# nf10_addon.net
KiCad netlist of a schematic drawn in Altium Designer
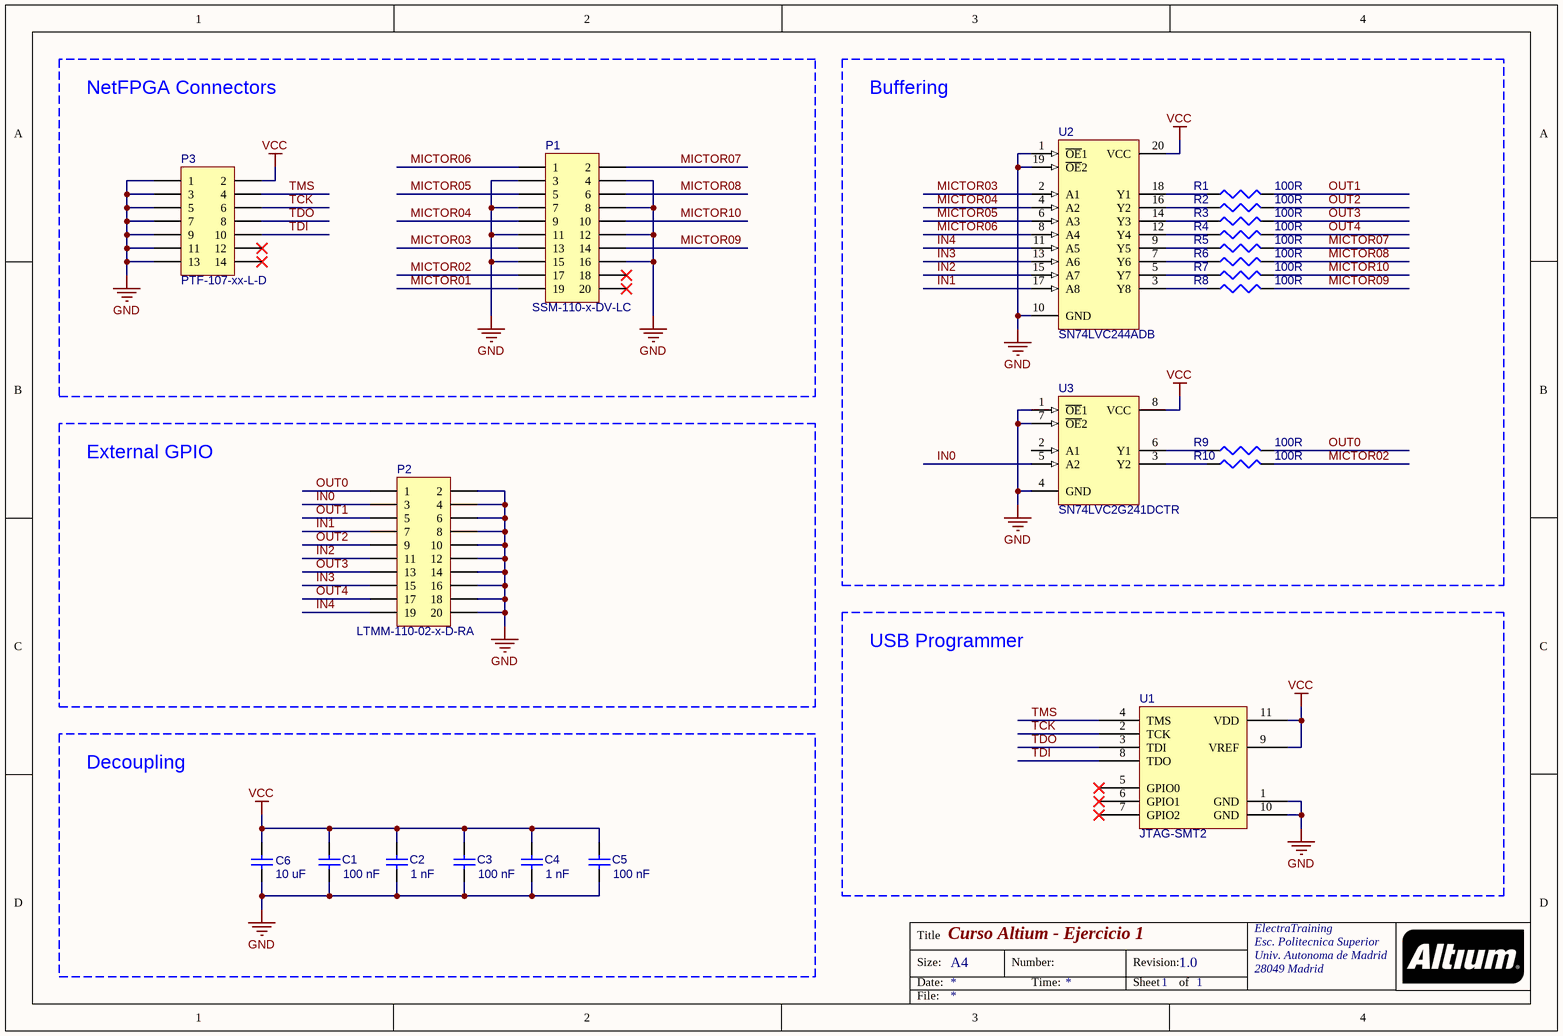
[diagram p0: nf10_addon.SchDoc]

(export (version "E")
  (design (tool "Eeschema 10.0.6"))
  (components
    (comp (ref "C1")
      (value "100 nF")
      (footprint "CAPC0603(1608)100_N")
      (description "Capacitor")
      (fields (field (name "Comment") "Cap") (field (name "PUBLISHER") "Altium Limited"))
      (libsource (lib "Miscellaneous Devices") (part "Cap"))
    )
    (comp (ref "C2")
      (value "1 nF")
      (footprint "CAPC0603(1608)100_N")
      (description "Capacitor")
      (fields (field (name "Comment") "Cap") (field (name "PUBLISHER") "Altium Limited"))
      (libsource (lib "Miscellaneous Devices") (part "Cap"))
    )
    (comp (ref "C3")
      (value "100 nF")
      (footprint "CAPC0603(1608)100_N")
      (description "Capacitor")
      (fields (field (name "Comment") "Cap") (field (name "PUBLISHER") "Altium Limited"))
      (libsource (lib "Miscellaneous Devices") (part "Cap"))
    )
    (comp (ref "C4")
      (value "1 nF")
      (footprint "CAPC0603(1608)100_N")
      (description "Capacitor")
      (fields (field (name "Comment") "Cap") (field (name "PUBLISHER") "Altium Limited"))
      (libsource (lib "Miscellaneous Devices") (part "Cap"))
    )
    (comp (ref "C5")
      (value "100 nF")
      (footprint "CAPC0603(1608)100_N")
      (description "Capacitor")
      (fields (field (name "Comment") "Cap") (field (name "PUBLISHER") "Altium Limited"))
      (libsource (lib "Miscellaneous Devices") (part "Cap"))
    )
    (comp (ref "C6")
      (value "10 uF")
      (footprint "CAPC1206(3216)100_N")
      (description "Capacitor")
      (fields (field (name "Comment") "Cap") (field (name "PUBLISHER") "Altium Limited"))
      (libsource (lib "Miscellaneous Devices") (part "Cap"))
    )
    (comp (ref "P1")
      (value "SSM-110-x-DV-LC")
      (footprint "SSM-110-X-DV-LC")
      (description "Samtec SSM-110-x-DV-LC")
      (fields (field (name "PUBLISHER") "Altium Limited"))
      (libsource (lib "nf10_addon") (part "SSM-110-x-DV-LC"))
    )
    (comp (ref "P2")
      (value "LTMM-110-02-x-D-RA")
      (footprint "LTMM-110-02-X-D-RA")
      (description "Samtec LTMM-110-02-x-D-RA")
      (fields (field (name "PUBLISHER") "Altium Limited"))
      (libsource (lib "nf10_addon") (part "LTMM-110-02-x-D-RA"))
    )
    (comp (ref "P3")
      (value "PTF-107-xx-L-D")
      (footprint "PTF-107-XX-L-D")
      (description "Samtec PTF-107-xx-L-D")
      (fields (field (name "PUBLISHER") "Altium Limited"))
      (libsource (lib "nf10_addon") (part "PTF-107-xx-L-D"))
    )
    (comp (ref "R1")
      (value "100R")
      (footprint "RESC0603(1608)_N")
      (description "Resistor")
      (fields (field (name "Comment") "Res3") (field (name "PUBLISHER") "Altium Limited"))
      (libsource (lib "Miscellaneous Devices") (part "Res3"))
    )
    (comp (ref "R2")
      (value "100R")
      (footprint "RESC0603(1608)_N")
      (description "Resistor")
      (fields (field (name "Comment") "Res3") (field (name "PUBLISHER") "Altium Limited"))
      (libsource (lib "Miscellaneous Devices") (part "Res3"))
    )
    (comp (ref "R3")
      (value "100R")
      (footprint "RESC0603(1608)_N")
      (description "Resistor")
      (fields (field (name "Comment") "Res3") (field (name "PUBLISHER") "Altium Limited"))
      (libsource (lib "Miscellaneous Devices") (part "Res3"))
    )
    (comp (ref "R4")
      (value "100R")
      (footprint "RESC0603(1608)_N")
      (description "Resistor")
      (fields (field (name "Comment") "Res3") (field (name "PUBLISHER") "Altium Limited"))
      (libsource (lib "Miscellaneous Devices") (part "Res3"))
    )
    (comp (ref "R5")
      (value "100R")
      (footprint "RESC0603(1608)_N")
      (description "Resistor")
      (fields (field (name "Comment") "Res3") (field (name "PUBLISHER") "Altium Limited"))
      (libsource (lib "Miscellaneous Devices") (part "Res3"))
    )
    (comp (ref "R6")
      (value "100R")
      (footprint "RESC0603(1608)_N")
      (description "Resistor")
      (fields (field (name "Comment") "Res3") (field (name "PUBLISHER") "Altium Limited"))
      (libsource (lib "Miscellaneous Devices") (part "Res3"))
    )
    (comp (ref "R7")
      (value "100R")
      (footprint "RESC0603(1608)_N")
      (description "Resistor")
      (fields (field (name "Comment") "Res3") (field (name "PUBLISHER") "Altium Limited"))
      (libsource (lib "Miscellaneous Devices") (part "Res3"))
    )
    (comp (ref "R8")
      (value "100R")
      (footprint "RESC0603(1608)_N")
      (description "Resistor")
      (fields (field (name "Comment") "Res3") (field (name "PUBLISHER") "Altium Limited"))
      (libsource (lib "Miscellaneous Devices") (part "Res3"))
    )
    (comp (ref "R9")
      (value "100R")
      (footprint "RESC0603(1608)_N")
      (description "Resistor")
      (fields (field (name "Comment") "Res3") (field (name "PUBLISHER") "Altium Limited"))
      (libsource (lib "Miscellaneous Devices") (part "Res3"))
    )
    (comp (ref "R10")
      (value "100R")
      (footprint "RESC0603(1608)_N")
      (description "Resistor")
      (fields (field (name "Comment") "Res3") (field (name "PUBLISHER") "Altium Limited"))
      (libsource (lib "Miscellaneous Devices") (part "Res3"))
    )
    (comp (ref "U1")
      (value "JTAG-SMT2")
      (footprint "JTAG-SMT2")
      (libsource (lib "NetFPGA10G_Addon") (part "JTAG_SMT2"))
    )
    (comp (ref "U2")
      (value "SN74LVC244ADB")
      (footprint "DB020_N")
      (description "Octal Buffer/Driver with 3-State Outputs")
      (fields (field (name "PUBLISHER") "Altium Limited"))
      (libsource (lib "TI Logic Buffer Line Driver") (part "SN74LVC244ADB"))
    )
    (comp (ref "U3")
      (value "SN74LVC2G241DCTR")
      (footprint "DCT08_N")
      (description "Quadruple Bus Buffer Gate with 3- State Outputs")
      (fields (field (name "PUBLISHER") "Altium Limited"))
      (libsource (lib "nf10_addon") (part "SN74LVC2G241DCTR"))
    )
  )
  (nets
    (net (code "1") (name "/IN0") (class "Default")
      (node (ref "P2") (pin "3") (pinfunction "3_3") (pintype "passive"))
      (node (ref "U3") (pin "5") (pinfunction "A2_5") (pintype "input"))
    )
    (net (code "2") (name "/IN1") (class "Default")
      (node (ref "P2") (pin "7") (pinfunction "7_7") (pintype "passive"))
      (node (ref "U2") (pin "17") (pinfunction "A8_17") (pintype "input"))
    )
    (net (code "3") (name "/IN2") (class "Default")
      (node (ref "P2") (pin "11") (pinfunction "11_11") (pintype "passive"))
      (node (ref "U2") (pin "15") (pinfunction "A7_15") (pintype "input"))
    )
    (net (code "4") (name "/IN3") (class "Default")
      (node (ref "P2") (pin "15") (pinfunction "15_15") (pintype "passive"))
      (node (ref "U2") (pin "13") (pinfunction "A6_13") (pintype "input"))
    )
    (net (code "5") (name "/IN4") (class "Default")
      (node (ref "P2") (pin "19") (pinfunction "19_19") (pintype "passive"))
      (node (ref "U2") (pin "11") (pinfunction "A5_11") (pintype "input"))
    )
    (net (code "6") (name "/MICTOR01") (class "Default")
      (node (ref "P1") (pin "19") (pinfunction "19_19") (pintype "passive"))
    )
    (net (code "7") (name "/MICTOR02") (class "Default")
      (node (ref "P1") (pin "17") (pinfunction "17_17") (pintype "passive"))
      (node (ref "R10") (pin "2") (pinfunction "2_2") (pintype "passive"))
    )
    (net (code "8") (name "/MICTOR03") (class "Default")
      (node (ref "P1") (pin "13") (pinfunction "13_13") (pintype "passive"))
      (node (ref "U2") (pin "2") (pinfunction "A1_2") (pintype "input"))
    )
    (net (code "9") (name "/MICTOR04") (class "Default")
      (node (ref "P1") (pin "9") (pinfunction "9_9") (pintype "passive"))
      (node (ref "U2") (pin "4") (pinfunction "A2_4") (pintype "input"))
    )
    (net (code "10") (name "/MICTOR05") (class "Default")
      (node (ref "P1") (pin "5") (pinfunction "5_5") (pintype "passive"))
      (node (ref "U2") (pin "6") (pinfunction "A3_6") (pintype "input"))
    )
    (net (code "11") (name "/MICTOR06") (class "Default")
      (node (ref "P1") (pin "1") (pinfunction "1_1") (pintype "passive"))
      (node (ref "U2") (pin "8") (pinfunction "A4_8") (pintype "input"))
    )
    (net (code "12") (name "/MICTOR07") (class "Default")
      (node (ref "P1") (pin "2") (pinfunction "2_2") (pintype "passive"))
      (node (ref "R5") (pin "2") (pinfunction "2_2") (pintype "passive"))
    )
    (net (code "13") (name "/MICTOR08") (class "Default")
      (node (ref "P1") (pin "6") (pinfunction "6_6") (pintype "passive"))
      (node (ref "R6") (pin "2") (pinfunction "2_2") (pintype "passive"))
    )
    (net (code "14") (name "/MICTOR09") (class "Default")
      (node (ref "P1") (pin "14") (pinfunction "14_14") (pintype "passive"))
      (node (ref "R8") (pin "2") (pinfunction "2_2") (pintype "passive"))
    )
    (net (code "15") (name "/MICTOR10") (class "Default")
      (node (ref "P1") (pin "10") (pinfunction "10_10") (pintype "passive"))
      (node (ref "R7") (pin "2") (pinfunction "2_2") (pintype "passive"))
    )
    (net (code "16") (name "/OUT0") (class "Default")
      (node (ref "P2") (pin "1") (pinfunction "1_1") (pintype "passive"))
      (node (ref "R9") (pin "2") (pinfunction "2_2") (pintype "passive"))
    )
    (net (code "17") (name "/OUT1") (class "Default")
      (node (ref "P2") (pin "5") (pinfunction "5_5") (pintype "passive"))
      (node (ref "R1") (pin "2") (pinfunction "2_2") (pintype "passive"))
    )
    (net (code "18") (name "/OUT2") (class "Default")
      (node (ref "P2") (pin "9") (pinfunction "9_9") (pintype "passive"))
      (node (ref "R2") (pin "2") (pinfunction "2_2") (pintype "passive"))
    )
    (net (code "19") (name "/OUT3") (class "Default")
      (node (ref "P2") (pin "13") (pinfunction "13_13") (pintype "passive"))
      (node (ref "R3") (pin "2") (pinfunction "2_2") (pintype "passive"))
    )
    (net (code "20") (name "/OUT4") (class "Default")
      (node (ref "P2") (pin "17") (pinfunction "17_17") (pintype "passive"))
      (node (ref "R4") (pin "2") (pinfunction "2_2") (pintype "passive"))
    )
    (net (code "21") (name "/TCK") (class "Default")
      (node (ref "P3") (pin "6") (pinfunction "6_6") (pintype "passive"))
      (node (ref "U1") (pin "2") (pinfunction "TCK_2") (pintype "passive"))
    )
    (net (code "22") (name "/TDI") (class "Default")
      (node (ref "P3") (pin "10") (pinfunction "10_10") (pintype "passive"))
      (node (ref "U1") (pin "8") (pinfunction "TDO_8") (pintype "passive"))
    )
    (net (code "23") (name "/TDO") (class "Default")
      (node (ref "P3") (pin "8") (pinfunction "8_8") (pintype "passive"))
      (node (ref "U1") (pin "3") (pinfunction "TDI_3") (pintype "passive"))
    )
    (net (code "24") (name "/TMS") (class "Default")
      (node (ref "P3") (pin "4") (pinfunction "4_4") (pintype "passive"))
      (node (ref "U1") (pin "4") (pinfunction "TMS_4") (pintype "passive"))
    )
    (net (code "25") (name "GND") (class "Default")
      (node (ref "C1") (pin "1") (pinfunction "1_1") (pintype "passive"))
      (node (ref "C2") (pin "1") (pinfunction "1_1") (pintype "passive"))
      (node (ref "C3") (pin "1") (pinfunction "1_1") (pintype "passive"))
      (node (ref "C4") (pin "1") (pinfunction "1_1") (pintype "passive"))
      (node (ref "C5") (pin "1") (pinfunction "1_1") (pintype "passive"))
      (node (ref "C6") (pin "1") (pinfunction "1_1") (pintype "passive"))
      (node (ref "P1") (pin "11") (pinfunction "11_11") (pintype "passive"))
      (node (ref "P1") (pin "12") (pinfunction "12_12") (pintype "passive"))
      (node (ref "P1") (pin "15") (pinfunction "15_15") (pintype "passive"))
      (node (ref "P1") (pin "16") (pinfunction "16_16") (pintype "passive"))
      (node (ref "P1") (pin "3") (pinfunction "3_3") (pintype "passive"))
      (node (ref "P1") (pin "4") (pinfunction "4_4") (pintype "passive"))
      (node (ref "P1") (pin "7") (pinfunction "7_7") (pintype "passive"))
      (node (ref "P1") (pin "8") (pinfunction "8_8") (pintype "passive"))
      (node (ref "P2") (pin "10") (pinfunction "10_10") (pintype "passive"))
      (node (ref "P2") (pin "12") (pinfunction "12_12") (pintype "passive"))
      (node (ref "P2") (pin "14") (pinfunction "14_14") (pintype "passive"))
      (node (ref "P2") (pin "16") (pinfunction "16_16") (pintype "passive"))
      (node (ref "P2") (pin "18") (pinfunction "18_18") (pintype "passive"))
      (node (ref "P2") (pin "2") (pinfunction "2_2") (pintype "passive"))
      (node (ref "P2") (pin "20") (pinfunction "20_20") (pintype "passive"))
      (node (ref "P2") (pin "4") (pinfunction "4_4") (pintype "passive"))
      (node (ref "P2") (pin "6") (pinfunction "6_6") (pintype "passive"))
      (node (ref "P2") (pin "8") (pinfunction "8_8") (pintype "passive"))
      (node (ref "P3") (pin "1") (pinfunction "1_1") (pintype "passive"))
      (node (ref "P3") (pin "11") (pinfunction "11_11") (pintype "passive"))
      (node (ref "P3") (pin "13") (pinfunction "13_13") (pintype "passive"))
      (node (ref "P3") (pin "3") (pinfunction "3_3") (pintype "passive"))
      (node (ref "P3") (pin "5") (pinfunction "5_5") (pintype "passive"))
      (node (ref "P3") (pin "7") (pinfunction "7_7") (pintype "passive"))
      (node (ref "P3") (pin "9") (pinfunction "9_9") (pintype "passive"))
      (node (ref "U1") (pin "1") (pinfunction "GND_1") (pintype "passive"))
      (node (ref "U1") (pin "10") (pinfunction "GND_10") (pintype "passive"))
      (node (ref "U2") (pin "1") (pinfunction "~{OE}1_1") (pintype "input"))
      (node (ref "U2") (pin "10") (pinfunction "GND_10") (pintype "power_in"))
      (node (ref "U2") (pin "19") (pinfunction "~{OE}2_19") (pintype "input"))
      (node (ref "U3") (pin "1") (pinfunction "~{OE}1_1") (pintype "input"))
      (node (ref "U3") (pin "4") (pinfunction "GND_4") (pintype "power_in"))
      (node (ref "U3") (pin "7") (pinfunction "~{OE}2_7") (pintype "input"))
    )
    (net (code "26") (name "Net-(U2-Y1)") (class "Default")
      (node (ref "R1") (pin "1") (pinfunction "1_1") (pintype "passive"))
      (node (ref "U2") (pin "18") (pinfunction "Y1_18") (pintype "tri_state"))
    )
    (net (code "27") (name "Net-(U2-Y2)") (class "Default")
      (node (ref "R2") (pin "1") (pinfunction "1_1") (pintype "passive"))
      (node (ref "U2") (pin "16") (pinfunction "Y2_16") (pintype "tri_state"))
    )
    (net (code "28") (name "Net-(U2-Y3)") (class "Default")
      (node (ref "R3") (pin "1") (pinfunction "1_1") (pintype "passive"))
      (node (ref "U2") (pin "14") (pinfunction "Y3_14") (pintype "tri_state"))
    )
    (net (code "29") (name "Net-(U2-Y4)") (class "Default")
      (node (ref "R4") (pin "1") (pinfunction "1_1") (pintype "passive"))
      (node (ref "U2") (pin "12") (pinfunction "Y4_12") (pintype "tri_state"))
    )
    (net (code "30") (name "Net-(U2-Y5)") (class "Default")
      (node (ref "R5") (pin "1") (pinfunction "1_1") (pintype "passive"))
      (node (ref "U2") (pin "9") (pinfunction "Y5_9") (pintype "tri_state"))
    )
    (net (code "31") (name "Net-(U2-Y6)") (class "Default")
      (node (ref "R6") (pin "1") (pinfunction "1_1") (pintype "passive"))
      (node (ref "U2") (pin "7") (pinfunction "Y6_7") (pintype "tri_state"))
    )
    (net (code "32") (name "Net-(U2-Y7)") (class "Default")
      (node (ref "R7") (pin "1") (pinfunction "1_1") (pintype "passive"))
      (node (ref "U2") (pin "5") (pinfunction "Y7_5") (pintype "tri_state"))
    )
    (net (code "33") (name "Net-(U2-Y8)") (class "Default")
      (node (ref "R8") (pin "1") (pinfunction "1_1") (pintype "passive"))
      (node (ref "U2") (pin "3") (pinfunction "Y8_3") (pintype "tri_state"))
    )
    (net (code "34") (name "Net-(U3-Y1)") (class "Default")
      (node (ref "R9") (pin "1") (pinfunction "1_1") (pintype "passive"))
      (node (ref "U3") (pin "6") (pinfunction "Y1_6") (pintype "tri_state"))
    )
    (net (code "35") (name "Net-(U3-Y2)") (class "Default")
      (node (ref "R10") (pin "1") (pinfunction "1_1") (pintype "passive"))
      (node (ref "U3") (pin "3") (pinfunction "Y2_3") (pintype "tri_state"))
    )
    (net (code "36") (name "VCC") (class "Default")
      (node (ref "C1") (pin "2") (pinfunction "2_2") (pintype "passive"))
      (node (ref "C2") (pin "2") (pinfunction "2_2") (pintype "passive"))
      (node (ref "C3") (pin "2") (pinfunction "2_2") (pintype "passive"))
      (node (ref "C4") (pin "2") (pinfunction "2_2") (pintype "passive"))
      (node (ref "C5") (pin "2") (pinfunction "2_2") (pintype "passive"))
      (node (ref "C6") (pin "2") (pinfunction "2_2") (pintype "passive"))
      (node (ref "P3") (pin "2") (pinfunction "2_2") (pintype "passive"))
      (node (ref "U1") (pin "11") (pinfunction "VDD_11") (pintype "passive"))
      (node (ref "U1") (pin "9") (pinfunction "VREF_9") (pintype "passive"))
      (node (ref "U2") (pin "20") (pinfunction "VCC_20") (pintype "power_in"))
      (node (ref "U3") (pin "8") (pinfunction "VCC_8") (pintype "power_in"))
    )
    (net (code "37") (name "unconnected-(P1-Pad18)") (class "Default")
      (node (ref "P1") (pin "18") (pinfunction "18_18") (pintype "passive+no_connect"))
    )
    (net (code "38") (name "unconnected-(P1-Pad20)") (class "Default")
      (node (ref "P1") (pin "20") (pinfunction "20_20") (pintype "passive+no_connect"))
    )
    (net (code "39") (name "unconnected-(P3-Pad12)") (class "Default")
      (node (ref "P3") (pin "12") (pinfunction "12_12") (pintype "passive+no_connect"))
    )
    (net (code "40") (name "unconnected-(P3-Pad14)") (class "Default")
      (node (ref "P3") (pin "14") (pinfunction "14_14") (pintype "passive+no_connect"))
    )
    (net (code "41") (name "unconnected-(U1-GPIO0-Pad5)") (class "Default")
      (node (ref "U1") (pin "5") (pinfunction "GPIO0_5") (pintype "passive+no_connect"))
    )
    (net (code "42") (name "unconnected-(U1-GPIO1-Pad6)") (class "Default")
      (node (ref "U1") (pin "6") (pinfunction "GPIO1_6") (pintype "passive+no_connect"))
    )
    (net (code "43") (name "unconnected-(U1-GPIO2-Pad7)") (class "Default")
      (node (ref "U1") (pin "7") (pinfunction "GPIO2_7") (pintype "passive+no_connect"))
    )
    (net (code "44") (name "unconnected-(U3-A1-Pad2)") (class "Default")
      (node (ref "U3") (pin "2") (pinfunction "A1_2") (pintype "input"))
    )
  )
)
